# TSOC_USBUART2_R2_0.net
KiCad netlist of a schematic drawn in EAGLE
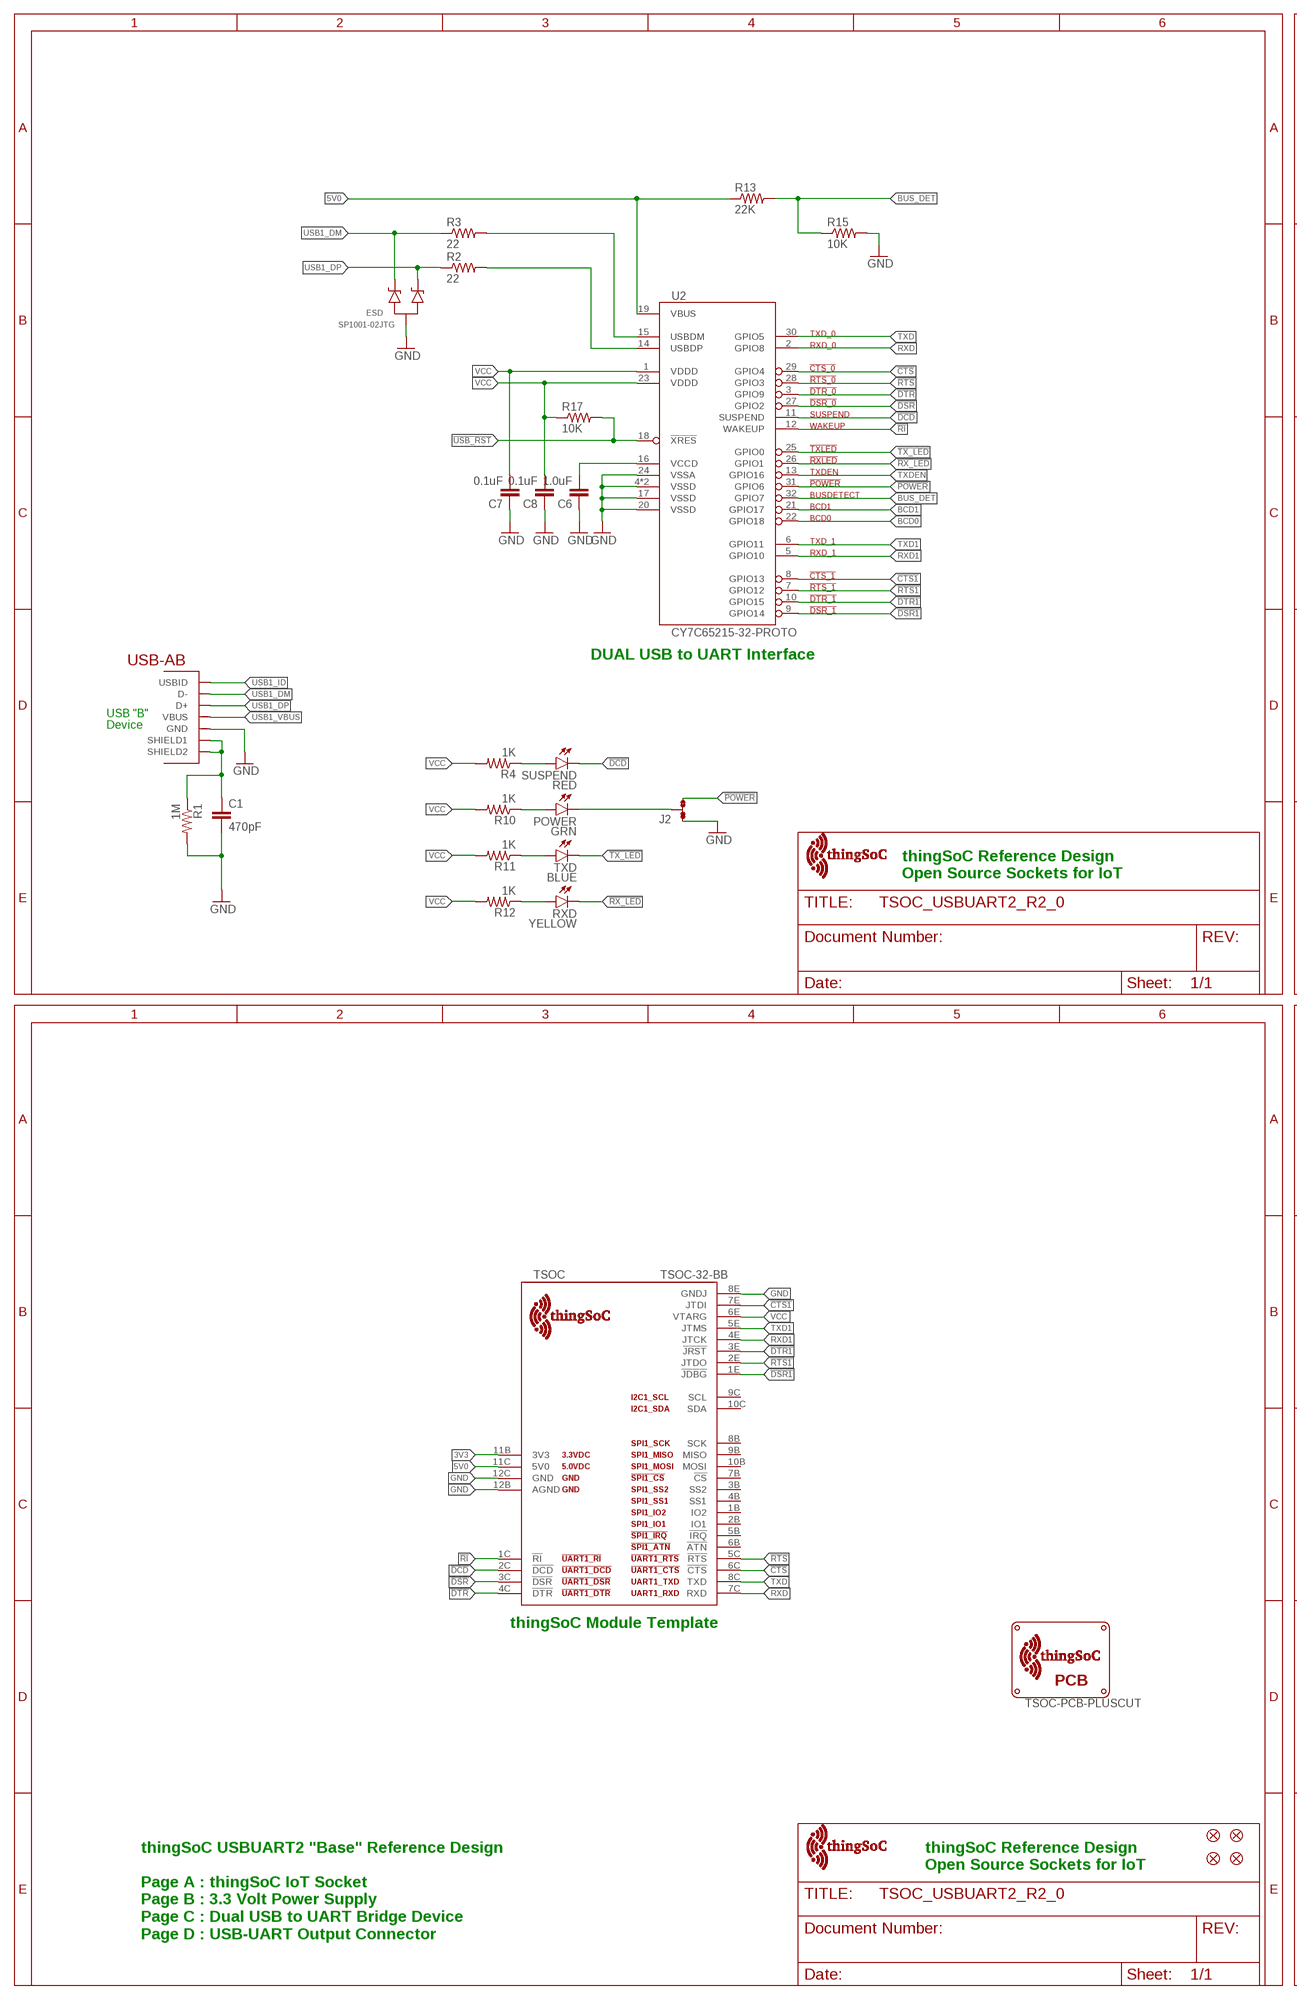
[diagram p0: schematic, sheet 1, part 1 of 2]
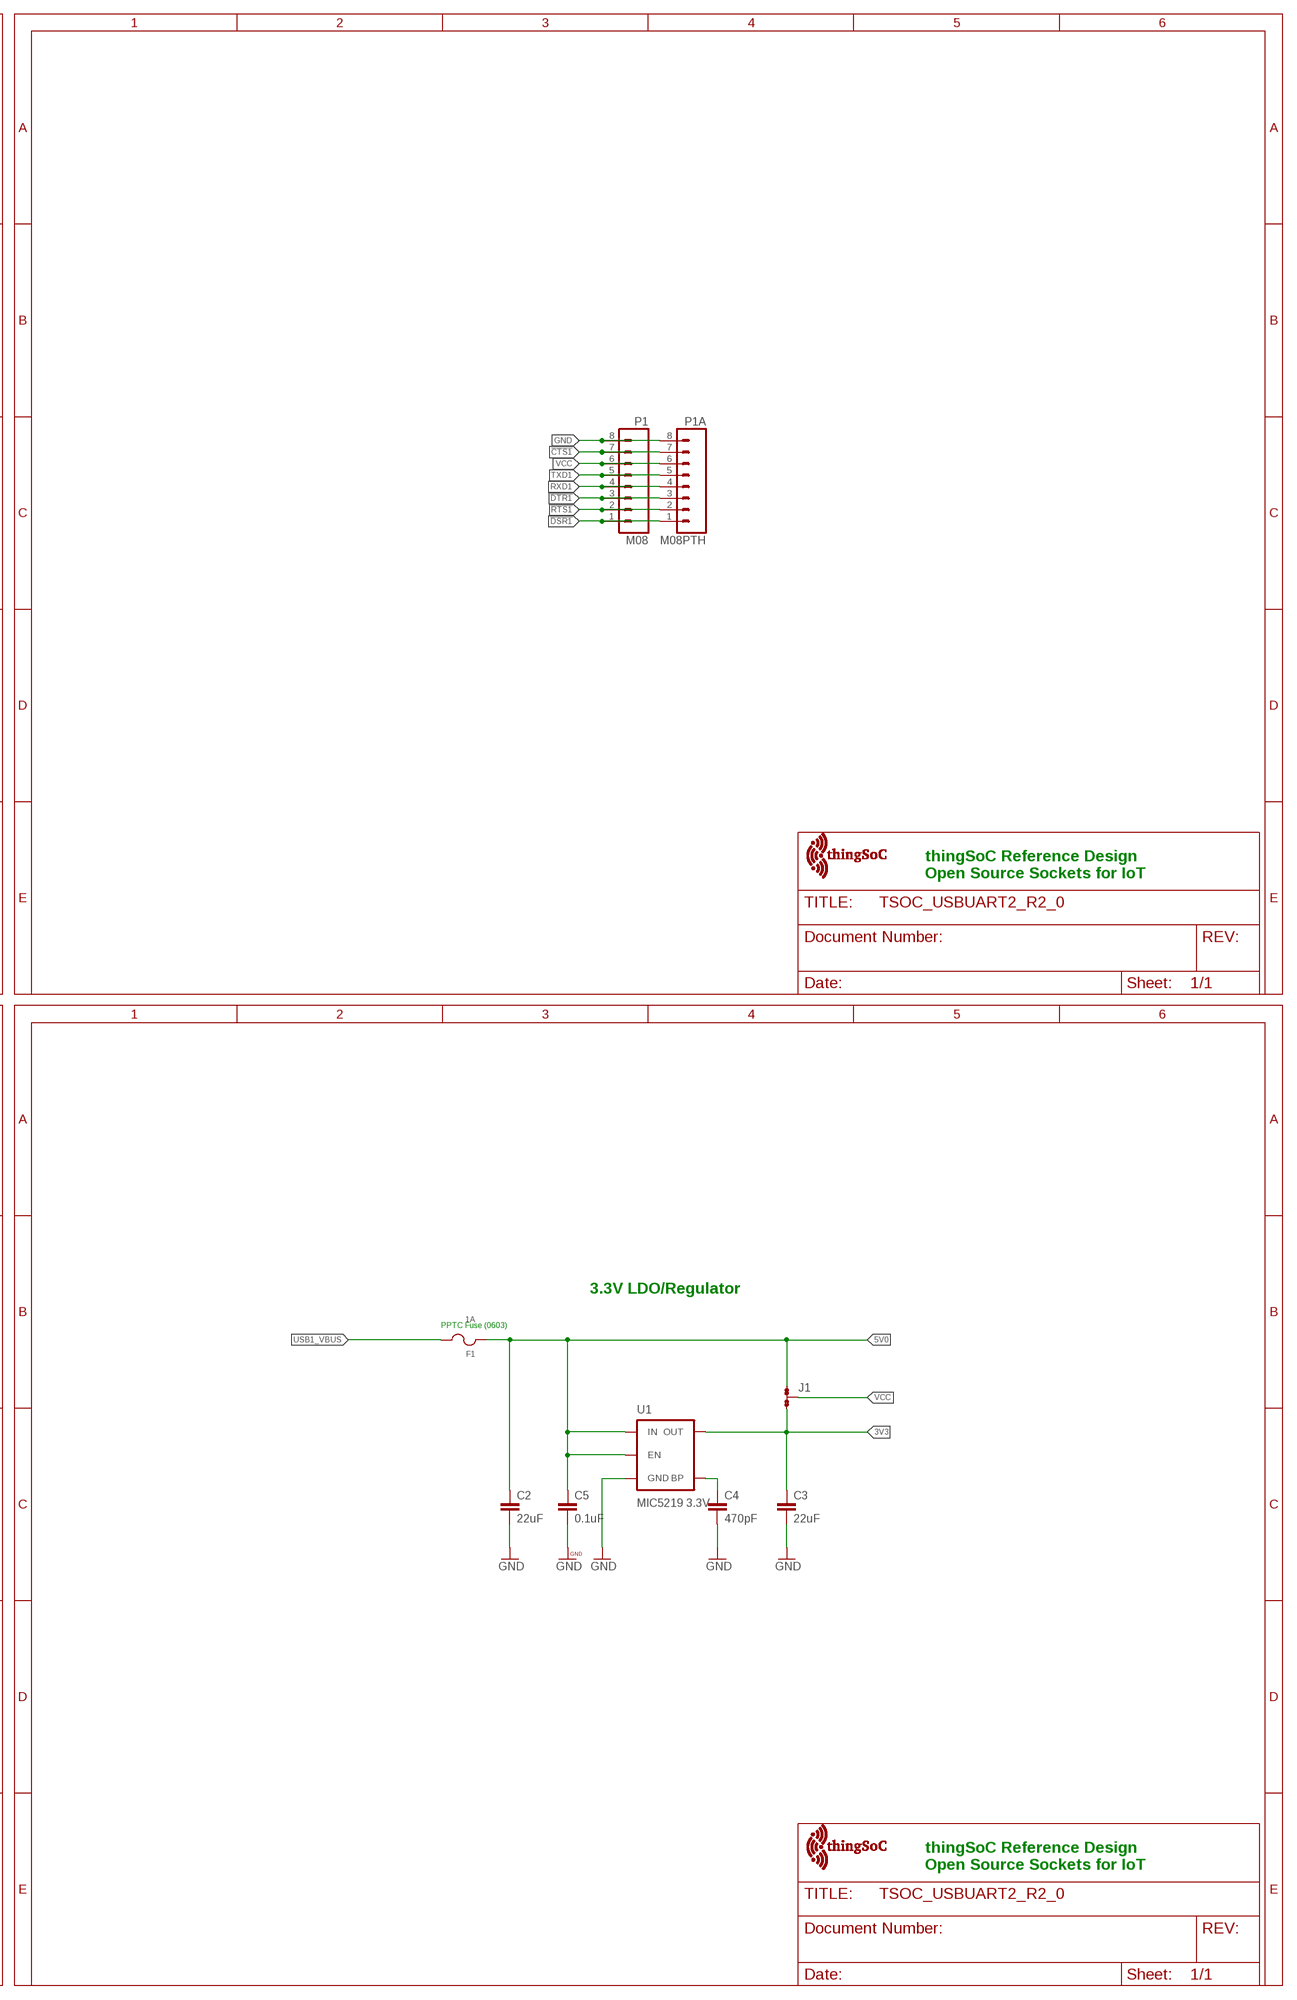
[diagram p1: schematic, sheet 1, part 2 of 2]

(export (version "E")
  (design (tool "Eeschema 10.0.6"))
  (components
    (comp (ref "C1")
      (value "470pF")
      (footprint "eagle-import:EIA-0603")
      (libsource (lib "eagle-import") (part "CAP-0603"))
    )
    (comp (ref "C2")
      (value "22uF")
      (footprint "eagle-import:EIA-1206")
      (libsource (lib "eagle-import") (part "CAP-1206"))
    )
    (comp (ref "C3")
      (value "22uF")
      (footprint "eagle-import:EIA-1206")
      (libsource (lib "eagle-import") (part "CAP-1206"))
    )
    (comp (ref "C4")
      (value "470pF")
      (footprint "eagle-import:EIA-0603")
      (libsource (lib "eagle-import") (part "CAP-0603"))
    )
    (comp (ref "C5")
      (value "0.1uF")
      (footprint "eagle-import:EIA-0603")
      (libsource (lib "eagle-import") (part "CAP-0603"))
    )
    (comp (ref "C6")
      (value "1.0uF")
      (footprint "eagle-import:EIA-0603")
      (libsource (lib "eagle-import") (part "CAP-0603"))
    )
    (comp (ref "C7")
      (value "0.1uF")
      (footprint "eagle-import:EIA-0603")
      (libsource (lib "eagle-import") (part "CAP-0603"))
    )
    (comp (ref "C8")
      (value "0.1uF")
      (footprint "eagle-import:EIA-0603")
      (libsource (lib "eagle-import") (part "CAP-0603"))
    )
    (comp (ref "ESD")
      (value "SP1001-02JTG")
      (footprint "eagle-import:SC70-3")
      (libsource (lib "eagle-import") (part "SP1001-02JTG"))
    )
    (comp (ref "F1")
      (value "1A")
      (footprint "eagle-import:EIA-0603")
      (libsource (lib "eagle-import") (part "FUSE"))
    )
    (comp (ref "FID1")
      (value "FIDUCIALUFIDUCIAL")
      (footprint "eagle-import:MICRO-FIDUCIAL")
      (libsource (lib "eagle-import") (part "FIDUCIALUFIDUCIAL"))
    )
    (comp (ref "FID2")
      (value "FIDUCIALUFIDUCIAL")
      (footprint "eagle-import:MICRO-FIDUCIAL")
      (libsource (lib "eagle-import") (part "FIDUCIALUFIDUCIAL"))
    )
    (comp (ref "FID3")
      (value "FIDUCIALUFIDUCIAL")
      (footprint "eagle-import:MICRO-FIDUCIAL")
      (libsource (lib "eagle-import") (part "FIDUCIALUFIDUCIAL"))
    )
    (comp (ref "FID4")
      (value "FIDUCIALUFIDUCIAL")
      (footprint "eagle-import:MICRO-FIDUCIAL")
      (libsource (lib "eagle-import") (part "FIDUCIALUFIDUCIAL"))
    )
    (comp (ref "J1")
      (value "JMP-3-1_2")
      (footprint "eagle-import:JMP-3-1_2")
      (libsource (lib "eagle-import") (part "JMP-3-1_2"))
    )
    (comp (ref "J2")
      (value "JMP-3-1_2")
      (footprint "eagle-import:JMP-3-1_2")
      (libsource (lib "eagle-import") (part "JMP-3-1_2"))
    )
    (comp (ref "P1")
      (value "M08")
      (footprint "eagle-import:1X08-SMD-FEMALE")
      (libsource (lib "eagle-import") (part "M08"))
    )
    (comp (ref "P1A")
      (value "M08PTH")
      (footprint "eagle-import:1X08")
      (libsource (lib "eagle-import") (part "M08PTH"))
    )
    (comp (ref "POWER")
      (value "GRN")
      (footprint "eagle-import:LED-0603")
      (libsource (lib "eagle-import") (part "LED0603"))
    )
    (comp (ref "R1")
      (value "1M")
      (footprint "eagle-import:EIA-0603")
      (libsource (lib "eagle-import") (part "RESISTOR-0603"))
    )
    (comp (ref "R2")
      (value "22")
      (footprint "eagle-import:EIA-0603")
      (libsource (lib "eagle-import") (part "RESISTOR-0603"))
    )
    (comp (ref "R3")
      (value "22")
      (footprint "eagle-import:EIA-0603")
      (libsource (lib "eagle-import") (part "RESISTOR-0603"))
    )
    (comp (ref "R4")
      (value "1K")
      (footprint "eagle-import:EIA-0603")
      (libsource (lib "eagle-import") (part "RESISTOR-0603"))
    )
    (comp (ref "R10")
      (value "1K")
      (footprint "eagle-import:EIA-0603")
      (libsource (lib "eagle-import") (part "RESISTOR-0603"))
    )
    (comp (ref "R11")
      (value "1K")
      (footprint "eagle-import:EIA-0603")
      (libsource (lib "eagle-import") (part "RESISTOR-0603"))
    )
    (comp (ref "R12")
      (value "1K")
      (footprint "eagle-import:EIA-0603")
      (libsource (lib "eagle-import") (part "RESISTOR-0603"))
    )
    (comp (ref "R13")
      (value "22K")
      (footprint "eagle-import:EIA-0603")
      (libsource (lib "eagle-import") (part "RESISTOR-0603"))
    )
    (comp (ref "R15")
      (value "10K")
      (footprint "eagle-import:EIA-0603")
      (libsource (lib "eagle-import") (part "RESISTOR-0603"))
    )
    (comp (ref "R17")
      (value "10K")
      (footprint "eagle-import:EIA-0603")
      (libsource (lib "eagle-import") (part "RESISTOR-0603"))
    )
    (comp (ref "RXD")
      (value "YELLOW")
      (footprint "eagle-import:LED-0603")
      (libsource (lib "eagle-import") (part "LED0603"))
    )
    (comp (ref "SUSPEND")
      (value "RED")
      (footprint "eagle-import:LED-0603")
      (libsource (lib "eagle-import") (part "LED0603"))
    )
    (comp (ref "TSOC")
      (value "TSOC-32-BB")
      (footprint "eagle-import:TSOC-BB-S32")
      (libsource (lib "eagle-import") (part "TSOC-32-BB"))
    )
    (comp (ref "TXD")
      (value "BLUE")
      (footprint "eagle-import:LED-0603")
      (libsource (lib "eagle-import") (part "LED0603"))
    )
    (comp (ref "U$3")
      (value "TSOC-LOGO-LRG")
      (footprint "eagle-import:TSOC-LOGO-LRG")
      (libsource (lib "eagle-import") (part "TSOC-LOGO-LRG"))
    )
    (comp (ref "U$4")
      (value "TSOC-LOGO")
      (footprint "eagle-import:TSOC-LOGO-BLANK")
      (libsource (lib "eagle-import") (part "TSOC-LOGO"))
    )
    (comp (ref "U$5")
      (value "TSOC-LOGO")
      (footprint "eagle-import:TSOC-LOGO-BLANK")
      (libsource (lib "eagle-import") (part "TSOC-LOGO"))
    )
    (comp (ref "U$6")
      (value "TSOC-LOGO")
      (footprint "eagle-import:TSOC-LOGO-BLANK")
      (libsource (lib "eagle-import") (part "TSOC-LOGO"))
    )
    (comp (ref "U$7")
      (value "TSOC-PCB-PLUSCUT")
      (footprint "eagle-import:TSOC-BB-BRD-PLUS-CUT")
      (libsource (lib "eagle-import") (part "TSOC-PCB-PLUSCUT"))
    )
    (comp (ref "U1")
      (value "MIC5219 3.3V")
      (footprint "eagle-import:SOT23-5")
      (libsource (lib "eagle-import") (part "V_REG_MIC52193.3V"))
    )
    (comp (ref "U2")
      (value "CY7C65215-32-PROTO")
      (footprint "eagle-import:QFN32-PROTO")
      (libsource (lib "eagle-import") (part "CY7C65215-32-PROTO"))
    )
    (comp (ref "USB")
      (value "USB_AB")
      (footprint "eagle-import:USB-AB-MICRO-SMD")
      (libsource (lib "eagle-import") (part "USB_AB"))
    )
  )
  (nets
    (net (code "1") (name "/~{CTS1}") (class "Default")
      (node (ref "P1") (pin "7") (pinfunction "7_7") (pintype "passive"))
      (node (ref "P1A") (pin "7") (pinfunction "7_7") (pintype "passive"))
      (node (ref "TSOC") (pin "7E") (pinfunction "JTDI_7E") (pintype "bidirectional"))
      (node (ref "U2") (pin "8") (pinfunction "GPIO13_8") (pintype "input"))
    )
    (net (code "2") (name "/~{CTS}") (class "Default")
      (node (ref "TSOC") (pin "6C") (pinfunction "~{CTS}_6C") (pintype "bidirectional"))
      (node (ref "U2") (pin "29") (pinfunction "GPIO4_29") (pintype "input"))
    )
    (net (code "3") (name "/~{DCD}") (class "Default")
      (node (ref "SUSPEND") (pin "C") (pinfunction "C_C") (pintype "passive"))
      (node (ref "TSOC") (pin "2C") (pinfunction "~{DCD}_2C") (pintype "bidirectional"))
      (node (ref "U2") (pin "11") (pinfunction "SUSPEND_11") (pintype "input"))
    )
    (net (code "4") (name "/~{DSR1}") (class "Default")
      (node (ref "P1") (pin "1") (pinfunction "1_1") (pintype "passive"))
      (node (ref "P1A") (pin "1") (pinfunction "1_1") (pintype "passive"))
      (node (ref "TSOC") (pin "1E") (pinfunction "~{JDBG}_1E") (pintype "bidirectional"))
      (node (ref "U2") (pin "9") (pinfunction "GPIO14_9") (pintype "input"))
    )
    (net (code "5") (name "/~{DSR}") (class "Default")
      (node (ref "TSOC") (pin "3C") (pinfunction "~{DSR}_3C") (pintype "bidirectional"))
      (node (ref "U2") (pin "27") (pinfunction "GPIO2_27") (pintype "input"))
    )
    (net (code "6") (name "/~{DTR1}") (class "Default")
      (node (ref "P1") (pin "3") (pinfunction "3_3") (pintype "passive"))
      (node (ref "P1A") (pin "3") (pinfunction "3_3") (pintype "passive"))
      (node (ref "TSOC") (pin "3E") (pinfunction "~{JRST}_3E") (pintype "bidirectional"))
      (node (ref "U2") (pin "10") (pinfunction "GPIO15_10") (pintype "output"))
    )
    (net (code "7") (name "/~{DTR}") (class "Default")
      (node (ref "TSOC") (pin "4C") (pinfunction "~{DTR}_4C") (pintype "bidirectional"))
      (node (ref "U2") (pin "3") (pinfunction "GPIO9_3") (pintype "output"))
    )
    (net (code "8") (name "/~{POWER}") (class "Default")
      (node (ref "J2") (pin "3") (pinfunction "3_3") (pintype "passive"))
      (node (ref "U2") (pin "31") (pinfunction "GPIO6_31") (pintype "input"))
    )
    (net (code "9") (name "/~{RI}") (class "Default")
      (node (ref "TSOC") (pin "1C") (pinfunction "~{RI}_1C") (pintype "bidirectional"))
      (node (ref "U2") (pin "12") (pinfunction "WAKEUP_12") (pintype "input"))
    )
    (net (code "10") (name "/~{RTS1}") (class "Default")
      (node (ref "P1") (pin "2") (pinfunction "2_2") (pintype "passive"))
      (node (ref "P1A") (pin "2") (pinfunction "2_2") (pintype "passive"))
      (node (ref "TSOC") (pin "2E") (pinfunction "JTDO_2E") (pintype "bidirectional"))
      (node (ref "U2") (pin "7") (pinfunction "GPIO12_7") (pintype "output"))
    )
    (net (code "11") (name "/~{RTS}") (class "Default")
      (node (ref "TSOC") (pin "5C") (pinfunction "~{RTS}_5C") (pintype "bidirectional"))
      (node (ref "U2") (pin "28") (pinfunction "GPIO3_28") (pintype "output"))
    )
    (net (code "12") (name "/~{RX_LED}") (class "Default")
      (node (ref "RXD") (pin "C") (pinfunction "C_C") (pintype "passive"))
      (node (ref "U2") (pin "26") (pinfunction "GPIO1_26") (pintype "input"))
    )
    (net (code "13") (name "/~{TX_LED}") (class "Default")
      (node (ref "TXD") (pin "C") (pinfunction "C_C") (pintype "passive"))
      (node (ref "U2") (pin "25") (pinfunction "GPIO0_25") (pintype "input"))
    )
    (net (code "14") (name "/~{USB_RST}") (class "Default")
      (node (ref "R17") (pin "2") (pinfunction "2_2") (pintype "passive"))
      (node (ref "U2") (pin "18") (pinfunction "~{XRES}_18") (pintype "input"))
    )
    (net (code "15") (name "3V3") (class "Default")
      (node (ref "C3") (pin "1") (pinfunction "1_1") (pintype "passive"))
      (node (ref "J1") (pin "3") (pinfunction "3_3") (pintype "passive"))
      (node (ref "TSOC") (pin "11B") (pinfunction "3V3_11B") (pintype "bidirectional"))
      (node (ref "U1") (pin "5") (pinfunction "OUT_5") (pintype "passive"))
    )
    (net (code "16") (name "5V0") (class "Default")
      (node (ref "C2") (pin "1") (pinfunction "1_1") (pintype "passive"))
      (node (ref "C5") (pin "1") (pinfunction "1_1") (pintype "passive"))
      (node (ref "F1") (pin "1") (pinfunction "P$1_1") (pintype "bidirectional"))
      (node (ref "J1") (pin "1") (pinfunction "1_1") (pintype "passive"))
      (node (ref "R13") (pin "1") (pinfunction "1_1") (pintype "passive"))
      (node (ref "TSOC") (pin "11C") (pinfunction "5V0_11C") (pintype "bidirectional"))
      (node (ref "U1") (pin "1") (pinfunction "IN_1") (pintype "input"))
      (node (ref "U1") (pin "3") (pinfunction "EN_3") (pintype "input"))
      (node (ref "U2") (pin "19") (pinfunction "VBUS_19") (pintype "power_in"))
    )
    (net (code "17") (name "BCD0") (class "Default")
      (node (ref "U2") (pin "22") (pinfunction "GPIO18_22") (pintype "input"))
    )
    (net (code "18") (name "BCD1") (class "Default")
      (node (ref "U2") (pin "21") (pinfunction "GPIO17_21") (pintype "input"))
    )
    (net (code "19") (name "BUS_DET") (class "Default")
      (node (ref "R13") (pin "2") (pinfunction "2_2") (pintype "passive"))
      (node (ref "R15") (pin "1") (pinfunction "1_1") (pintype "passive"))
      (node (ref "U2") (pin "32") (pinfunction "GPIO7_32") (pintype "input"))
    )
    (net (code "20") (name "GND") (class "Default")
      (node (ref "C1") (pin "2") (pinfunction "2_2") (pintype "passive"))
      (node (ref "C2") (pin "2") (pinfunction "2_2") (pintype "passive"))
      (node (ref "C3") (pin "2") (pinfunction "2_2") (pintype "passive"))
      (node (ref "C4") (pin "2") (pinfunction "2_2") (pintype "passive"))
      (node (ref "C5") (pin "2") (pinfunction "2_2") (pintype "passive"))
      (node (ref "C6") (pin "1") (pinfunction "1_1") (pintype "passive"))
      (node (ref "C7") (pin "1") (pinfunction "1_1") (pintype "passive"))
      (node (ref "C8") (pin "1") (pinfunction "1_1") (pintype "passive"))
      (node (ref "ESD") (pin "3") (pinfunction "A_3") (pintype "passive"))
      (node (ref "J2") (pin "1") (pinfunction "1_1") (pintype "passive"))
      (node (ref "P1") (pin "8") (pinfunction "8_8") (pintype "passive"))
      (node (ref "P1A") (pin "8") (pinfunction "8_8") (pintype "passive"))
      (node (ref "R1") (pin "2") (pinfunction "2_2") (pintype "passive"))
      (node (ref "R15") (pin "2") (pinfunction "2_2") (pintype "passive"))
      (node (ref "TSOC") (pin "12B") (pinfunction "AGND_12B") (pintype "bidirectional"))
      (node (ref "TSOC") (pin "12C") (pinfunction "GND_12C") (pintype "bidirectional"))
      (node (ref "TSOC") (pin "8E") (pinfunction "GNDJ_8E") (pintype "bidirectional"))
      (node (ref "U1") (pin "2") (pinfunction "GND_2") (pintype "input"))
      (node (ref "U2") (pin "17") (pinfunction "VSSD_17") (pintype "power_in"))
      (node (ref "U2") (pin "20") (pinfunction "VSSD_20") (pintype "power_in"))
      (node (ref "U2") (pin "24") (pinfunction "VSSA_24") (pintype "power_in"))
      (node (ref "U2") (pin "4") (pinfunction "VSSD_4") (pintype "power_in"))
      (node (ref "U2") (pin "EXP") (pinfunction "VSSD_EXP") (pintype "power_in"))
      (node (ref "USB") (pin "GND") (pinfunction "GND_GND") (pintype "bidirectional"))
    )
    (net (code "21") (name "Net-(C1-Pad1)") (class "Default")
      (node (ref "C1") (pin "1") (pinfunction "1_1") (pintype "passive"))
      (node (ref "R1") (pin "1") (pinfunction "1_1") (pintype "passive"))
      (node (ref "USB") (pin "SHIELD1") (pinfunction "SHIELD1_SHIELD1") (pintype "bidirectional"))
      (node (ref "USB") (pin "SHIELD2") (pinfunction "SHIELD2_SHIELD2") (pintype "bidirectional"))
    )
    (net (code "22") (name "Net-(J2-Pad2)") (class "Default")
      (node (ref "J2") (pin "2") (pinfunction "2_2") (pintype "passive"))
      (node (ref "POWER") (pin "C") (pinfunction "C_C") (pintype "passive"))
    )
    (net (code "23") (name "Net-(POWER-PadA)") (class "Default")
      (node (ref "POWER") (pin "A") (pinfunction "A_A") (pintype "passive"))
      (node (ref "R10") (pin "1") (pinfunction "1_1") (pintype "passive"))
    )
    (net (code "24") (name "Net-(R4-Pad1)") (class "Default")
      (node (ref "R4") (pin "1") (pinfunction "1_1") (pintype "passive"))
      (node (ref "SUSPEND") (pin "A") (pinfunction "A_A") (pintype "passive"))
    )
    (net (code "25") (name "Net-(R11-Pad1)") (class "Default")
      (node (ref "R11") (pin "1") (pinfunction "1_1") (pintype "passive"))
      (node (ref "TXD") (pin "A") (pinfunction "A_A") (pintype "passive"))
    )
    (net (code "26") (name "Net-(R12-Pad1)") (class "Default")
      (node (ref "R12") (pin "1") (pinfunction "1_1") (pintype "passive"))
      (node (ref "RXD") (pin "A") (pinfunction "A_A") (pintype "passive"))
    )
    (net (code "27") (name "Net-(U1-BP)") (class "Default")
      (node (ref "C4") (pin "1") (pinfunction "1_1") (pintype "passive"))
      (node (ref "U1") (pin "4") (pinfunction "BP_4") (pintype "input"))
    )
    (net (code "28") (name "Net-(U2-USBDM)") (class "Default")
      (node (ref "R3") (pin "2") (pinfunction "2_2") (pintype "passive"))
      (node (ref "U2") (pin "15") (pinfunction "USBDM_15") (pintype "bidirectional"))
    )
    (net (code "29") (name "Net-(U2-USBDP)") (class "Default")
      (node (ref "R2") (pin "2") (pinfunction "2_2") (pintype "passive"))
      (node (ref "U2") (pin "14") (pinfunction "USBDP_14") (pintype "bidirectional"))
    )
    (net (code "30") (name "Net-(U2-VCCD)") (class "Default")
      (node (ref "C6") (pin "2") (pinfunction "2_2") (pintype "passive"))
      (node (ref "U2") (pin "16") (pinfunction "VCCD_16") (pintype "output"))
    )
    (net (code "31") (name "RXD") (class "Default")
      (node (ref "TSOC") (pin "7C") (pinfunction "RXD_7C") (pintype "bidirectional"))
      (node (ref "U2") (pin "2") (pinfunction "GPIO8_2") (pintype "input"))
    )
    (net (code "32") (name "RXD1") (class "Default")
      (node (ref "P1") (pin "4") (pinfunction "4_4") (pintype "passive"))
      (node (ref "P1A") (pin "4") (pinfunction "4_4") (pintype "passive"))
      (node (ref "TSOC") (pin "4E") (pinfunction "JTCK_4E") (pintype "bidirectional"))
      (node (ref "U2") (pin "5") (pinfunction "GPIO10_5") (pintype "input"))
    )
    (net (code "33") (name "TXD") (class "Default")
      (node (ref "TSOC") (pin "8C") (pinfunction "TXD_8C") (pintype "bidirectional"))
      (node (ref "U2") (pin "30") (pinfunction "GPIO5_30") (pintype "output"))
    )
    (net (code "34") (name "TXD1") (class "Default")
      (node (ref "P1") (pin "5") (pinfunction "5_5") (pintype "passive"))
      (node (ref "P1A") (pin "5") (pinfunction "5_5") (pintype "passive"))
      (node (ref "TSOC") (pin "5E") (pinfunction "JTMS_5E") (pintype "bidirectional"))
      (node (ref "U2") (pin "6") (pinfunction "GPIO11_6") (pintype "output"))
    )
    (net (code "35") (name "TXDEN") (class "Default")
      (node (ref "U2") (pin "13") (pinfunction "GPIO16_13") (pintype "output"))
    )
    (net (code "36") (name "USB1_DM") (class "Default")
      (node (ref "ESD") (pin "2") (pinfunction "C2_2") (pintype "passive"))
      (node (ref "R3") (pin "1") (pinfunction "1_1") (pintype "passive"))
      (node (ref "USB") (pin "D-") (pinfunction "D-_D-") (pintype "bidirectional"))
    )
    (net (code "37") (name "USB1_DP") (class "Default")
      (node (ref "ESD") (pin "1") (pinfunction "C1_1") (pintype "passive"))
      (node (ref "R2") (pin "1") (pinfunction "1_1") (pintype "passive"))
      (node (ref "USB") (pin "D+") (pinfunction "D+_D+") (pintype "bidirectional"))
    )
    (net (code "38") (name "USB1_ID") (class "Default")
      (node (ref "USB") (pin "ID") (pinfunction "USBID_ID") (pintype "bidirectional"))
    )
    (net (code "39") (name "USB1_VBUS") (class "Default")
      (node (ref "F1") (pin "2") (pinfunction "P$2_2") (pintype "bidirectional"))
      (node (ref "USB") (pin "VBUS") (pinfunction "VBUS_VBUS") (pintype "bidirectional"))
    )
    (net (code "40") (name "VCC") (class "Default")
      (node (ref "C7") (pin "2") (pinfunction "2_2") (pintype "passive"))
      (node (ref "C8") (pin "2") (pinfunction "2_2") (pintype "passive"))
      (node (ref "J1") (pin "2") (pinfunction "2_2") (pintype "passive"))
      (node (ref "P1") (pin "6") (pinfunction "6_6") (pintype "passive"))
      (node (ref "P1A") (pin "6") (pinfunction "6_6") (pintype "passive"))
      (node (ref "R10") (pin "2") (pinfunction "2_2") (pintype "passive"))
      (node (ref "R11") (pin "2") (pinfunction "2_2") (pintype "passive"))
      (node (ref "R12") (pin "2") (pinfunction "2_2") (pintype "passive"))
      (node (ref "R17") (pin "1") (pinfunction "1_1") (pintype "passive"))
      (node (ref "R4") (pin "2") (pinfunction "2_2") (pintype "passive"))
      (node (ref "TSOC") (pin "6E") (pinfunction "VTARG_6E") (pintype "bidirectional"))
      (node (ref "U2") (pin "1") (pinfunction "VDDD_1") (pintype "power_in"))
      (node (ref "U2") (pin "23") (pinfunction "VDDD_23") (pintype "power_in"))
    )
    (net (code "41") (name "unconnected-(TSOC-IO1-Pad2B)") (class "Default")
      (node (ref "TSOC") (pin "2B") (pinfunction "IO1_2B") (pintype "bidirectional"))
    )
    (net (code "42") (name "unconnected-(TSOC-IO2-Pad1B)") (class "Default")
      (node (ref "TSOC") (pin "1B") (pinfunction "IO2_1B") (pintype "bidirectional"))
    )
    (net (code "43") (name "unconnected-(TSOC-MISO-Pad9B)") (class "Default")
      (node (ref "TSOC") (pin "9B") (pinfunction "MISO_9B") (pintype "bidirectional"))
    )
    (net (code "44") (name "unconnected-(TSOC-MOSI-Pad10B)") (class "Default")
      (node (ref "TSOC") (pin "10B") (pinfunction "MOSI_10B") (pintype "bidirectional"))
    )
    (net (code "45") (name "unconnected-(TSOC-SCK-Pad8B)") (class "Default")
      (node (ref "TSOC") (pin "8B") (pinfunction "SCK_8B") (pintype "bidirectional"))
    )
    (net (code "46") (name "unconnected-(TSOC-SCL-Pad9C)") (class "Default")
      (node (ref "TSOC") (pin "9C") (pinfunction "SCL_9C") (pintype "bidirectional"))
    )
    (net (code "47") (name "unconnected-(TSOC-SDA-Pad10C)") (class "Default")
      (node (ref "TSOC") (pin "10C") (pinfunction "SDA_10C") (pintype "bidirectional"))
    )
    (net (code "48") (name "unconnected-(TSOC-SS1-Pad4B)") (class "Default")
      (node (ref "TSOC") (pin "4B") (pinfunction "SS1_4B") (pintype "bidirectional"))
    )
    (net (code "49") (name "unconnected-(TSOC-SS2-Pad3B)") (class "Default")
      (node (ref "TSOC") (pin "3B") (pinfunction "SS2_3B") (pintype "bidirectional"))
    )
    (net (code "50") (name "unconnected-(TSOC-~{ATN}-Pad6B)") (class "Default")
      (node (ref "TSOC") (pin "6B") (pinfunction "~{ATN}_6B") (pintype "bidirectional"))
    )
    (net (code "51") (name "unconnected-(TSOC-~{CS}-Pad7B)") (class "Default")
      (node (ref "TSOC") (pin "7B") (pinfunction "~{CS}_7B") (pintype "bidirectional"))
    )
    (net (code "52") (name "unconnected-(TSOC-~{IRQ}-Pad5B)") (class "Default")
      (node (ref "TSOC") (pin "5B") (pinfunction "~{IRQ}_5B") (pintype "bidirectional"))
    )
  )
)
